# Power.net
KiCad netlist of a schematic drawn in Altium Designer
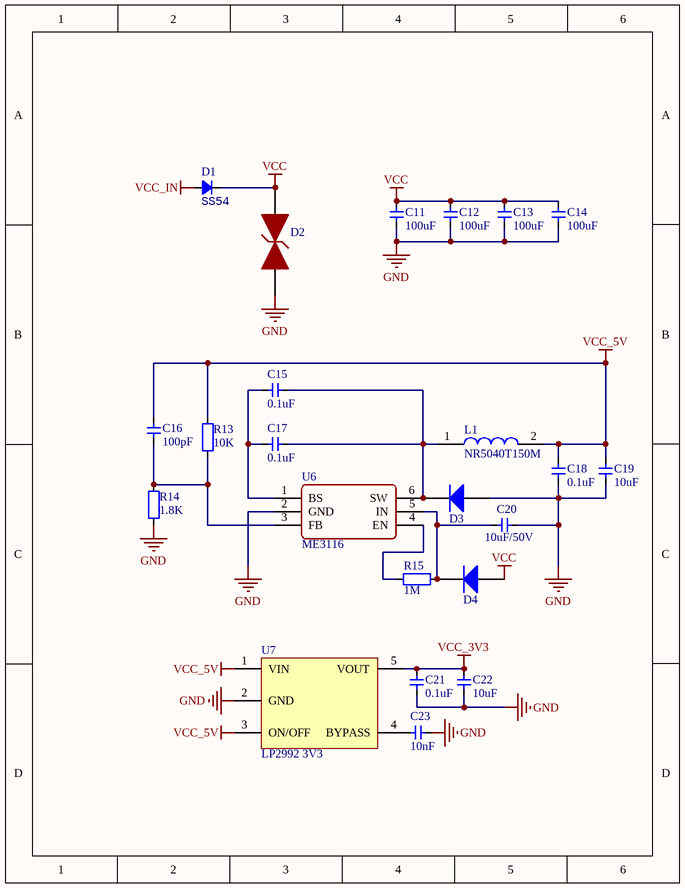
[diagram p0: Power.SchDoc]

(export (version "E")
  (design (tool "Eeschema 10.0.6"))
  (components
    (comp (ref "C11")
      (value "100uF")
      (footprint "1206-CAP")
      (description "Capacitor")
      (libsource (lib "MyPcbLib") (part "电容-1206"))
    )
    (comp (ref "C12")
      (value "100uF")
      (footprint "1206-CAP")
      (description "Capacitor")
      (libsource (lib "MyPcbLib") (part "电容-1206"))
    )
    (comp (ref "C13")
      (value "100uF")
      (footprint "1206-CAP")
      (description "Capacitor")
      (libsource (lib "MyPcbLib") (part "电容-1206"))
    )
    (comp (ref "C14")
      (value "100uF")
      (footprint "1206-CAP")
      (description "Capacitor")
      (libsource (lib "MyPcbLib") (part "电容-1206"))
    )
    (comp (ref "C15")
      (value "0.1uF")
      (footprint "CAP_0402")
      (description "Capacitor")
      (libsource (lib "MyPcbLib") (part "电容-0402"))
    )
    (comp (ref "C16")
      (value "100pF")
      (footprint "CAP_0402")
      (description "Capacitor")
      (libsource (lib "MyPcbLib") (part "电容-0402"))
    )
    (comp (ref "C17")
      (value "0.1uF")
      (footprint "CAP_0402")
      (description "Capacitor")
      (libsource (lib "MyPcbLib") (part "电容-0402"))
    )
    (comp (ref "C18")
      (value "0.1uF")
      (footprint "CAP_0402")
      (description "Capacitor")
      (libsource (lib "MyPcbLib") (part "电容-0402"))
    )
    (comp (ref "C19")
      (value "10uF")
      (footprint "CAP_0402")
      (description "Capacitor")
      (libsource (lib "MyPcbLib") (part "电容-0402"))
    )
    (comp (ref "C20")
      (value "10uF/50V")
      (footprint "CAP_0402")
      (description "Capacitor")
      (libsource (lib "MyPcbLib") (part "电容-0402"))
    )
    (comp (ref "C21")
      (value "0.1uF")
      (footprint "CAP_0402")
      (description "Capacitor")
      (libsource (lib "MyPcbLib") (part "电容-0402"))
    )
    (comp (ref "C22")
      (value "10uF")
      (footprint "CAP_0402")
      (description "Capacitor")
      (libsource (lib "MyPcbLib") (part "电容-0402"))
    )
    (comp (ref "C23")
      (value "10nF")
      (footprint "CAP_0402")
      (description "Capacitor")
      (libsource (lib "MyPcbLib") (part "电容-0402"))
    )
    (comp (ref "D1")
      (value "SS54")
      (footprint "DO-214AC")
      (description "Diode")
      (libsource (lib "KitSprout") (part "Diode_SMA"))
    )
    (comp (ref "D2")
      (value "SMBJ28CA")
      (footprint "SMBJ-CA_MFG")
      (libsource (lib "MyPcbLib") (part "SMBJ28CA"))
    )
    (comp (ref "D3")
      (value "二极管-5819W")
      (footprint "SOD-323")
      (description "40V")
      (libsource (lib "MyPcbLib") (part "二极管-5819W"))
    )
    (comp (ref "D4")
      (value "二极管-5819W")
      (footprint "SOD-323")
      (description "40V")
      (libsource (lib "MyPcbLib") (part "二极管-5819W"))
    )
    (comp (ref "L1")
      (value "NR5040T150M")
      (footprint "SamacSys:NR5040T150M")
      (description "Inductor")
      (fields (field (name "MOUSER PART NUMBER") "963-NR5040T150M"))
      (libsource (lib "SamacSys") (part "NR5040T150M"))
    )
    (comp (ref "R13")
      (value "10K")
      (footprint "RES_0402")
      (description "Resistor")
      (libsource (lib "MyPcbLib") (part "电阻-0402"))
    )
    (comp (ref "R14")
      (value "1.8K")
      (footprint "RES_0402")
      (description "Resistor")
      (libsource (lib "MyPcbLib") (part "电阻-0402"))
    )
    (comp (ref "R15")
      (value "1M")
      (footprint "RES_0402")
      (description "Resistor")
      (libsource (lib "") (part "电阻-0402_1"))
    )
    (comp (ref "U6")
      (value "ME3116")
      (footprint "SOT23-6")
      (description "DC-DC")
      (libsource (lib "MyPcbLib") (part "ME3116"))
    )
    (comp (ref "U7")
      (value "LP2992 3V3")
      (footprint "SOT23-5")
      (description "LDO")
      (libsource (lib "MyPcbLib") (part "LP2992"))
    )
  )
  (nets
    (net (code "1") (name "GND") (class "Default")
      (node (ref "C11") (pin "1") (pinfunction "1_1") (pintype "passive"))
      (node (ref "C12") (pin "1") (pinfunction "1_1") (pintype "passive"))
      (node (ref "C13") (pin "1") (pinfunction "1_1") (pintype "passive"))
      (node (ref "C14") (pin "1") (pinfunction "1_1") (pintype "passive"))
      (node (ref "C18") (pin "1") (pinfunction "1_1") (pintype "passive"))
      (node (ref "C19") (pin "1") (pinfunction "1_1") (pintype "passive"))
      (node (ref "C20") (pin "1") (pinfunction "1_1") (pintype "passive"))
      (node (ref "C21") (pin "1") (pinfunction "1_1") (pintype "passive"))
      (node (ref "C22") (pin "1") (pinfunction "1_1") (pintype "passive"))
      (node (ref "C23") (pin "1") (pinfunction "1_1") (pintype "passive"))
      (node (ref "D2") (pin "1") (pinfunction "1_1") (pintype "passive"))
      (node (ref "D3") (pin "1") (pinfunction "A_1") (pintype "passive"))
      (node (ref "R14") (pin "1") (pinfunction "1_1") (pintype "passive"))
      (node (ref "U6") (pin "2") (pinfunction "GND_2") (pintype "passive"))
      (node (ref "U7") (pin "2") (pinfunction "GND_2") (pintype "passive"))
    )
    (net (code "2") (name "Net-(D3-K)") (class "Default")
      (node (ref "C15") (pin "1") (pinfunction "1_1") (pintype "passive"))
      (node (ref "C17") (pin "1") (pinfunction "1_1") (pintype "passive"))
      (node (ref "D3") (pin "2") (pinfunction "K_2") (pintype "passive"))
      (node (ref "L1") (pin "1") (pinfunction "1_1") (pintype "passive"))
      (node (ref "U6") (pin "6") (pinfunction "SW_6") (pintype "passive"))
    )
    (net (code "3") (name "Net-(D4-K)") (class "Default")
      (node (ref "C20") (pin "2") (pinfunction "2_2") (pintype "passive"))
      (node (ref "D4") (pin "2") (pinfunction "K_2") (pintype "passive"))
      (node (ref "R15") (pin "1") (pinfunction "1_1") (pintype "passive"))
      (node (ref "U6") (pin "5") (pinfunction "IN_5") (pintype "passive"))
    )
    (net (code "4") (name "Net-(U6-BS)") (class "Default")
      (node (ref "C15") (pin "2") (pinfunction "2_2") (pintype "passive"))
      (node (ref "C17") (pin "2") (pinfunction "2_2") (pintype "passive"))
      (node (ref "U6") (pin "1") (pinfunction "BS_1") (pintype "passive"))
    )
    (net (code "5") (name "Net-(U6-EN)") (class "Default")
      (node (ref "R15") (pin "2") (pinfunction "2_2") (pintype "passive"))
      (node (ref "U6") (pin "4") (pinfunction "EN_4") (pintype "passive"))
    )
    (net (code "6") (name "Net-(U6-FB)") (class "Default")
      (node (ref "C16") (pin "2") (pinfunction "2_2") (pintype "passive"))
      (node (ref "R13") (pin "1") (pinfunction "1_1") (pintype "passive"))
      (node (ref "R14") (pin "2") (pinfunction "2_2") (pintype "passive"))
      (node (ref "U6") (pin "3") (pinfunction "FB_3") (pintype "passive"))
    )
    (net (code "7") (name "Net-(U7-BYPASS)") (class "Default")
      (node (ref "C23") (pin "2") (pinfunction "2_2") (pintype "passive"))
      (node (ref "U7") (pin "4") (pinfunction "BYPASS_4") (pintype "passive"))
    )
    (net (code "8") (name "VCC") (class "Default")
      (node (ref "C11") (pin "2") (pinfunction "2_2") (pintype "passive"))
      (node (ref "C12") (pin "2") (pinfunction "2_2") (pintype "passive"))
      (node (ref "C13") (pin "2") (pinfunction "2_2") (pintype "passive"))
      (node (ref "C14") (pin "2") (pinfunction "2_2") (pintype "passive"))
      (node (ref "D1") (pin "2") (pinfunction "K_2") (pintype "passive"))
      (node (ref "D2") (pin "2") (pinfunction "2_2") (pintype "passive"))
      (node (ref "D4") (pin "1") (pinfunction "A_1") (pintype "passive"))
    )
    (net (code "9") (name "VCC_3V3") (class "Default")
      (node (ref "C21") (pin "2") (pinfunction "2_2") (pintype "passive"))
      (node (ref "C22") (pin "2") (pinfunction "2_2") (pintype "passive"))
      (node (ref "U7") (pin "5") (pinfunction "VOUT_5") (pintype "passive"))
    )
    (net (code "10") (name "VCC_5V") (class "Default")
      (node (ref "C16") (pin "1") (pinfunction "1_1") (pintype "passive"))
      (node (ref "C18") (pin "2") (pinfunction "2_2") (pintype "passive"))
      (node (ref "C19") (pin "2") (pinfunction "2_2") (pintype "passive"))
      (node (ref "L1") (pin "2") (pinfunction "2_2") (pintype "passive"))
      (node (ref "R13") (pin "2") (pinfunction "2_2") (pintype "passive"))
      (node (ref "U7") (pin "1") (pinfunction "VIN_1") (pintype "passive"))
      (node (ref "U7") (pin "3") (pinfunction "ON/OFF_3") (pintype "passive"))
    )
    (net (code "11") (name "VCC_IN") (class "Default")
      (node (ref "D1") (pin "1") (pinfunction "A_1") (pintype "passive"))
    )
  )
)
